# Clock_Divider.net
KiCad netlist of a schematic drawn in Altium Designer
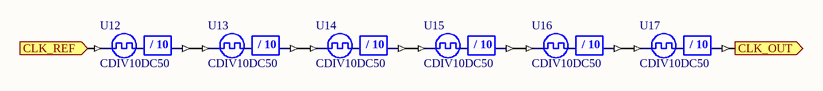
[diagram p0: Clock_Divider.SchDoc]

(export (version "E")
  (design (tool "Eeschema 10.0.6"))
  (components
    (comp (ref "U12")
      (value "CDIV10DC50")
      (description "Clock Divider by 10 with 50% Duty Cycle Output")
      (fields (field (name "PUBLISHER") "Altium Limited"))
      (libsource (lib "FPGA Generic") (part "CDIV10DC50"))
    )
    (comp (ref "U13")
      (value "CDIV10DC50")
      (description "Clock Divider by 10 with 50% Duty Cycle Output")
      (fields (field (name "PUBLISHER") "Altium Limited"))
      (libsource (lib "FPGA Generic") (part "CDIV10DC50"))
    )
    (comp (ref "U14")
      (value "CDIV10DC50")
      (description "Clock Divider by 10 with 50% Duty Cycle Output")
      (fields (field (name "PUBLISHER") "Altium Limited"))
      (libsource (lib "FPGA Generic") (part "CDIV10DC50"))
    )
    (comp (ref "U15")
      (value "CDIV10DC50")
      (description "Clock Divider by 10 with 50% Duty Cycle Output")
      (fields (field (name "PUBLISHER") "Altium Limited"))
      (libsource (lib "FPGA Generic") (part "CDIV10DC50"))
    )
    (comp (ref "U16")
      (value "CDIV10DC50")
      (description "Clock Divider by 10 with 50% Duty Cycle Output")
      (fields (field (name "PUBLISHER") "Altium Limited"))
      (libsource (lib "FPGA Generic") (part "CDIV10DC50"))
    )
    (comp (ref "U17")
      (value "CDIV10DC50")
      (description "Clock Divider by 10 with 50% Duty Cycle Output")
      (fields (field (name "PUBLISHER") "Altium Limited"))
      (libsource (lib "FPGA Generic") (part "CDIV10DC50"))
    )
  )
  (nets
    (net (code "1") (name "/CLK_OUT") (class "Default")
      (node (ref "U17") (pin "CLKDV") (pinfunction "CLKDV_CLKDV") (pintype "output"))
    )
    (net (code "2") (name "/CLK_REF") (class "Default")
      (node (ref "U12") (pin "CLKIN") (pinfunction "CLKIN_CLKIN") (pintype "input"))
    )
    (net (code "3") (name "Net-(U12-PadCLKDV)") (class "Default")
      (node (ref "U12") (pin "CLKDV") (pinfunction "CLKDV_CLKDV") (pintype "output"))
      (node (ref "U13") (pin "CLKIN") (pinfunction "CLKIN_CLKIN") (pintype "input"))
    )
    (net (code "4") (name "Net-(U13-PadCLKDV)") (class "Default")
      (node (ref "U13") (pin "CLKDV") (pinfunction "CLKDV_CLKDV") (pintype "output"))
      (node (ref "U14") (pin "CLKIN") (pinfunction "CLKIN_CLKIN") (pintype "input"))
    )
    (net (code "5") (name "Net-(U14-PadCLKDV)") (class "Default")
      (node (ref "U14") (pin "CLKDV") (pinfunction "CLKDV_CLKDV") (pintype "output"))
      (node (ref "U15") (pin "CLKIN") (pinfunction "CLKIN_CLKIN") (pintype "input"))
    )
    (net (code "6") (name "Net-(U15-PadCLKDV)") (class "Default")
      (node (ref "U15") (pin "CLKDV") (pinfunction "CLKDV_CLKDV") (pintype "output"))
      (node (ref "U16") (pin "CLKIN") (pinfunction "CLKIN_CLKIN") (pintype "input"))
    )
    (net (code "7") (name "Net-(U16-PadCLKDV)") (class "Default")
      (node (ref "U16") (pin "CLKDV") (pinfunction "CLKDV_CLKDV") (pintype "output"))
      (node (ref "U17") (pin "CLKIN") (pinfunction "CLKIN_CLKIN") (pintype "input"))
    )
  )
)
